# bbf-audio_out.net
KiCad netlist of a schematic drawn in EAGLE
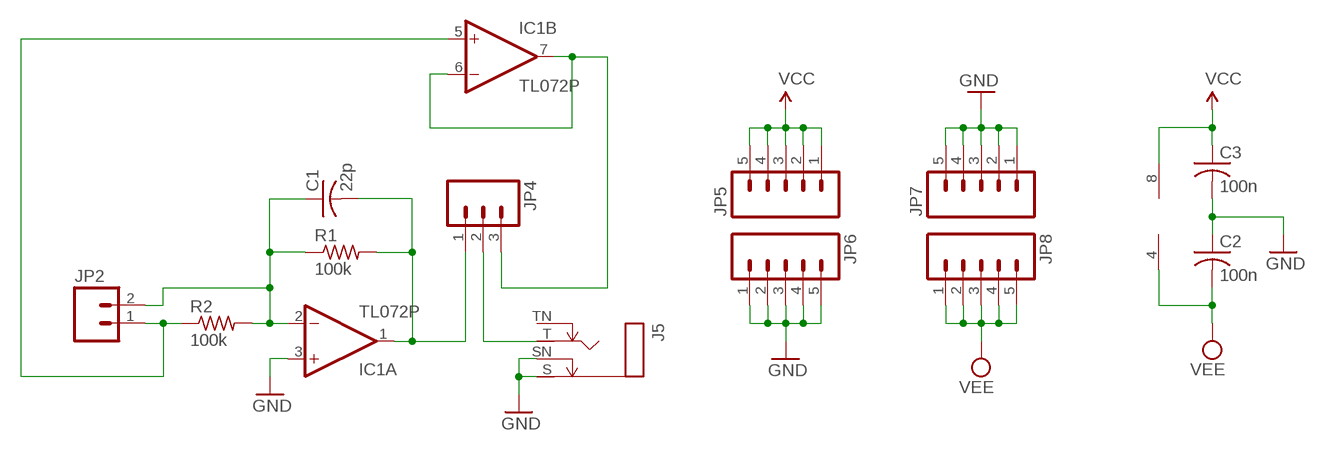
[diagram p0: schematic, sheet 1]

(export (version "E")
  (design (tool "Eeschema 10.0.6"))
  (components
    (comp (ref "C1")
      (value "22p")
      (footprint "eagle-import:C025-025X050")
      (libsource (lib "eagle-import") (part "C-US025-025X050"))
    )
    (comp (ref "C2")
      (value "100n")
      (footprint "eagle-import:C025-025X050")
      (libsource (lib "eagle-import") (part "C-US025-025X050"))
    )
    (comp (ref "C3")
      (value "100n")
      (footprint "eagle-import:C025-025X050")
      (libsource (lib "eagle-import") (part "C-US025-025X050"))
    )
    (comp (ref "IC1")
      (value "TL072P")
      (footprint "eagle-import:DIL08")
      (libsource (lib "eagle-import") (part "TL072P"))
    )
    (comp (ref "J5")
      (value "MONOSWSLIM")
      (footprint "eagle-import:NRJ4HF")
      (libsource (lib "eagle-import") (part "MONOSWSLIM"))
    )
    (comp (ref "JP2")
      (value "M02PTH")
      (footprint "eagle-import:1X02")
      (libsource (lib "eagle-import") (part "M02PTH"))
    )
    (comp (ref "JP4")
      (value "M03PTH")
      (footprint "eagle-import:1X03")
      (libsource (lib "eagle-import") (part "M03PTH"))
    )
    (comp (ref "JP5")
      (value "M05PTH")
      (footprint "eagle-import:1X05")
      (libsource (lib "eagle-import") (part "M05PTH"))
    )
    (comp (ref "JP6")
      (value "M05PTH")
      (footprint "eagle-import:1X05")
      (libsource (lib "eagle-import") (part "M05PTH"))
    )
    (comp (ref "JP7")
      (value "M05PTH")
      (footprint "eagle-import:1X05")
      (libsource (lib "eagle-import") (part "M05PTH"))
    )
    (comp (ref "JP8")
      (value "M05PTH")
      (footprint "eagle-import:1X05")
      (libsource (lib "eagle-import") (part "M05PTH"))
    )
    (comp (ref "R1")
      (value "100k")
      (footprint "eagle-import:0204_7")
      (libsource (lib "eagle-import") (part "R-US_0204/7"))
    )
    (comp (ref "R2")
      (value "100k")
      (footprint "eagle-import:0204_7")
      (libsource (lib "eagle-import") (part "R-US_0204/7"))
    )
  )
  (nets
    (net (code "1") (name "GND") (class "Default")
      (node (ref "C2") (pin "1") (pinfunction "1_1") (pintype "passive"))
      (node (ref "C3") (pin "2") (pinfunction "2_2") (pintype "passive"))
      (node (ref "IC1") (pin "3") (pinfunction "+IN_3") (pintype "input"))
      (node (ref "J5") (pin "S") (pinfunction "S_S") (pintype "passive"))
      (node (ref "J5") (pin "SN") (pinfunction "SN_SN") (pintype "passive"))
      (node (ref "JP6") (pin "1") (pinfunction "1_1") (pintype "passive"))
      (node (ref "JP6") (pin "2") (pinfunction "2_2") (pintype "passive"))
      (node (ref "JP6") (pin "3") (pinfunction "3_3") (pintype "passive"))
      (node (ref "JP6") (pin "4") (pinfunction "4_4") (pintype "passive"))
      (node (ref "JP6") (pin "5") (pinfunction "5_5") (pintype "passive"))
      (node (ref "JP7") (pin "1") (pinfunction "1_1") (pintype "passive"))
      (node (ref "JP7") (pin "2") (pinfunction "2_2") (pintype "passive"))
      (node (ref "JP7") (pin "3") (pinfunction "3_3") (pintype "passive"))
      (node (ref "JP7") (pin "4") (pinfunction "4_4") (pintype "passive"))
      (node (ref "JP7") (pin "5") (pinfunction "5_5") (pintype "passive"))
    )
    (net (code "2") (name "Net-(IC1A--IN)") (class "Default")
      (node (ref "C1") (pin "1") (pinfunction "1_1") (pintype "passive"))
      (node (ref "IC1") (pin "2") (pinfunction "-IN_2") (pintype "input"))
      (node (ref "JP2") (pin "2") (pinfunction "2_2") (pintype "passive"))
      (node (ref "R1") (pin "1") (pinfunction "1_1") (pintype "passive"))
      (node (ref "R2") (pin "2") (pinfunction "2_2") (pintype "passive"))
    )
    (net (code "3") (name "Net-(IC1A-OUT)") (class "Default")
      (node (ref "C1") (pin "2") (pinfunction "2_2") (pintype "passive"))
      (node (ref "IC1") (pin "1") (pinfunction "OUT_1") (pintype "output"))
      (node (ref "JP4") (pin "1") (pinfunction "1_1") (pintype "passive"))
      (node (ref "R1") (pin "2") (pinfunction "2_2") (pintype "passive"))
    )
    (net (code "4") (name "Net-(IC1B-+IN)") (class "Default")
      (node (ref "IC1") (pin "5") (pinfunction "+IN_5") (pintype "input"))
      (node (ref "JP2") (pin "1") (pinfunction "1_1") (pintype "passive"))
      (node (ref "R2") (pin "1") (pinfunction "1_1") (pintype "passive"))
    )
    (net (code "5") (name "Net-(IC1B--IN)") (class "Default")
      (node (ref "IC1") (pin "6") (pinfunction "-IN_6") (pintype "input"))
      (node (ref "IC1") (pin "7") (pinfunction "OUT_7") (pintype "output"))
      (node (ref "JP4") (pin "3") (pinfunction "3_3") (pintype "passive"))
    )
    (net (code "6") (name "Net-(J5-PadT)") (class "Default")
      (node (ref "J5") (pin "T") (pinfunction "T_T") (pintype "passive"))
      (node (ref "JP4") (pin "2") (pinfunction "2_2") (pintype "passive"))
    )
    (net (code "7") (name "VCC") (class "Default")
      (node (ref "C3") (pin "1") (pinfunction "1_1") (pintype "passive"))
      (node (ref "IC1") (pin "8") (pinfunction "V+_8") (pintype "power_in"))
      (node (ref "JP5") (pin "1") (pinfunction "1_1") (pintype "passive"))
      (node (ref "JP5") (pin "2") (pinfunction "2_2") (pintype "passive"))
      (node (ref "JP5") (pin "3") (pinfunction "3_3") (pintype "passive"))
      (node (ref "JP5") (pin "4") (pinfunction "4_4") (pintype "passive"))
      (node (ref "JP5") (pin "5") (pinfunction "5_5") (pintype "passive"))
    )
    (net (code "8") (name "VEE") (class "Default")
      (node (ref "C2") (pin "2") (pinfunction "2_2") (pintype "passive"))
      (node (ref "IC1") (pin "4") (pinfunction "V-_4") (pintype "power_in"))
      (node (ref "JP8") (pin "1") (pinfunction "1_1") (pintype "passive"))
      (node (ref "JP8") (pin "2") (pinfunction "2_2") (pintype "passive"))
      (node (ref "JP8") (pin "3") (pinfunction "3_3") (pintype "passive"))
      (node (ref "JP8") (pin "4") (pinfunction "4_4") (pintype "passive"))
      (node (ref "JP8") (pin "5") (pinfunction "5_5") (pintype "passive"))
    )
    (net (code "9") (name "unconnected-(J5-PadTN)") (class "Default")
      (node (ref "J5") (pin "TN") (pinfunction "TN_TN") (pintype "passive"))
    )
  )
)
